# custom_hat_v_alpha.net
KiCad netlist of a schematic drawn in EAGLE
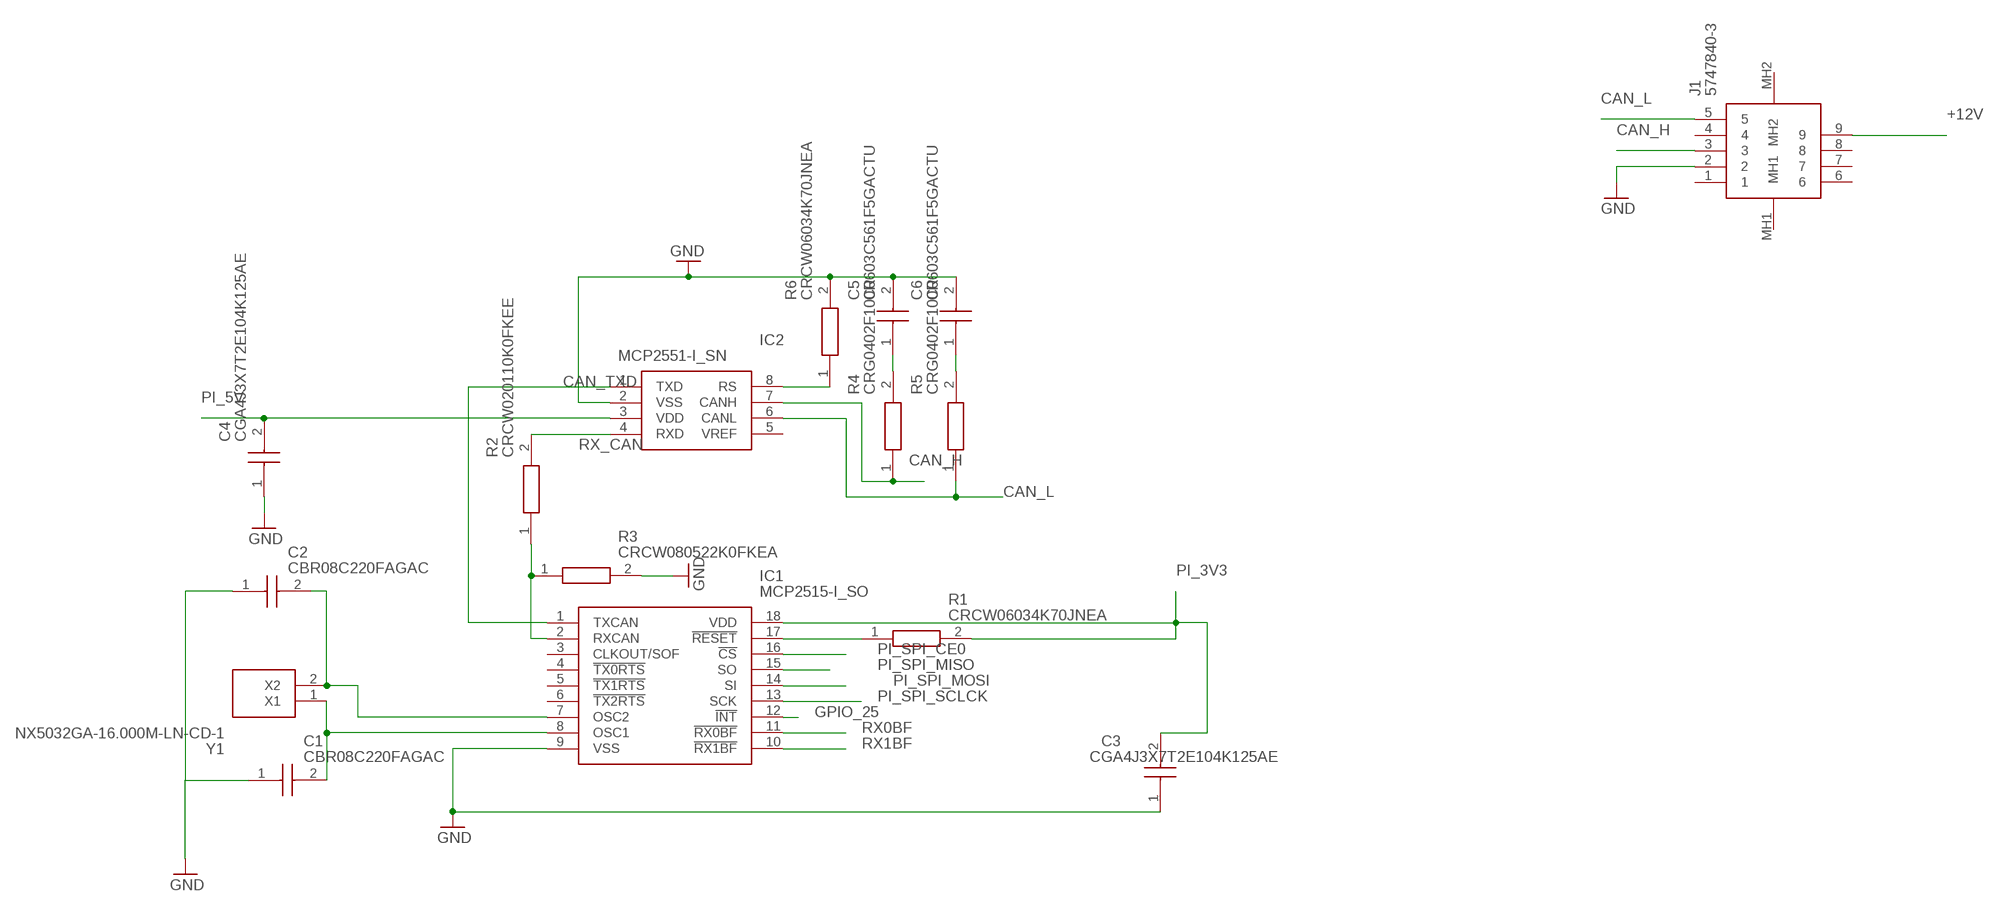
[diagram p0: schematic, sheet 1]

(export (version "E")
  (design (tool "Eeschema 10.0.6"))
  (components
    (comp (ref "C1")
      (value "CBR08C220FAGAC")
      (footprint "eagle-import:CAPC2012X95N")
      (libsource (lib "eagle-import") (part "CBR08C220FAGAC"))
    )
    (comp (ref "C2")
      (value "CBR08C220FAGAC")
      (footprint "eagle-import:CAPC2012X95N")
      (libsource (lib "eagle-import") (part "CBR08C220FAGAC"))
    )
    (comp (ref "C3")
      (value "CGA4J3X7T2E104K125AE")
      (footprint "eagle-import:CAPC2012X145N")
      (fields (field (name "MOUSER_PART_NUMBER") "810-CGA4J3X7T2E104KS"))
      (libsource (lib "eagle-import") (part "CGA4J3X7T2E104K125AE"))
    )
    (comp (ref "C4")
      (value "CGA4J3X7T2E104K125AE")
      (footprint "eagle-import:CAPC2012X145N")
      (fields (field (name "MOUSER_PART_NUMBER") "810-CGA4J3X7T2E104KS"))
      (libsource (lib "eagle-import") (part "CGA4J3X7T2E104K125AE"))
    )
    (comp (ref "C5")
      (value "C0603C561F5GACTU")
      (footprint "eagle-import:CAPC1608X87N")
      (fields (field (name "MOUSER_PART_NUMBER") "80-C0603C561F5G"))
      (libsource (lib "eagle-import") (part "C0603C561F5GACTU"))
    )
    (comp (ref "C6")
      (value "C0603C561F5GACTU")
      (footprint "eagle-import:CAPC1608X87N")
      (fields (field (name "MOUSER_PART_NUMBER") "80-C0603C561F5G"))
      (libsource (lib "eagle-import") (part "C0603C561F5GACTU"))
    )
    (comp (ref "IC1")
      (value "MCP2515-I_SO")
      (footprint "eagle-import:SOIC127P1030X265-18N")
      (fields
        (field (name "ARROW_PART_NUMBER") "MCP2515-I/SO")
        (field (name "MOUSER_PART_NUMBER") "579-MCP2515-I/SO")
      )
      (libsource (lib "eagle-import") (part "MCP2515-I_SO"))
    )
    (comp (ref "IC2")
      (value "MCP2551-I_SN")
      (footprint "eagle-import:SOIC127P600X175-8N")
      (fields
        (field (name "ARROW_PART_NUMBER") "MCP2551-I/SN")
        (field (name "MOUSER_PART_NUMBER") "579-MCP2551-I/SN")
      )
      (libsource (lib "eagle-import") (part "MCP2551-I_SN"))
    )
    (comp (ref "J1")
      (value "5747840-3")
      (footprint "eagle-import:57478403")
      (fields (field (name "MOUSER_PART_NUMBER") "571-5747840-3"))
      (libsource (lib "eagle-import") (part "5747840-3"))
    )
    (comp (ref "R1")
      (value "CRCW06034K70JNEA")
      (footprint "eagle-import:RESC1608X50N")
      (fields (field (name "MOUSER_PART_NUMBER") "71-CRCW0603J-4.7K-E3"))
      (libsource (lib "eagle-import") (part "CRCW06034K70JNEA"))
    )
    (comp (ref "R2")
      (value "CRCW020110K0FKEE")
      (footprint "eagle-import:RESC0603X28N")
      (libsource (lib "eagle-import") (part "CRCW020110K0FKEE"))
    )
    (comp (ref "R3")
      (value "CRCW080522K0FKEA")
      (footprint "eagle-import:RESC2012X50N")
      (fields (field (name "MOUSER_PART_NUMBER") "71-CRCW0805-22K-E3"))
      (libsource (lib "eagle-import") (part "CRCW080522K0FKEA"))
    )
    (comp (ref "R4")
      (value "CRG0402F100R")
      (footprint "eagle-import:RESC1005X40N")
      (fields (field (name "MOUSER_PART_NUMBER") "279-CRG0402F100R"))
      (libsource (lib "eagle-import") (part "CRG0402F100R"))
    )
    (comp (ref "R5")
      (value "CRG0402F100R")
      (footprint "eagle-import:RESC1005X40N")
      (fields (field (name "MOUSER_PART_NUMBER") "279-CRG0402F100R"))
      (libsource (lib "eagle-import") (part "CRG0402F100R"))
    )
    (comp (ref "R6")
      (value "CRCW06034K70JNEA")
      (footprint "eagle-import:RESC1608X50N")
      (fields (field (name "MOUSER_PART_NUMBER") "71-CRCW0603J-4.7K-E3"))
      (libsource (lib "eagle-import") (part "CRCW06034K70JNEA"))
    )
    (comp (ref "Y1")
      (value "NX5032GA-16.000M-LN-CD-1")
      (footprint "eagle-import:NX5032GA16000000MHZLNCD1")
      (fields (field (name "MOUSER_PART_NUMBER") "344-NX5032GA16MLNCD1"))
      (libsource (lib "eagle-import") (part "NX5032GA-16.000M-LN-CD-1"))
    )
  )
  (nets
    (net (code "1") (name "/+12V") (class "Default")
      (node (ref "J1") (pin "9") (pinfunction "9_9") (pintype "bidirectional"))
    )
    (net (code "2") (name "/CAN_H") (class "Default")
      (node (ref "IC2") (pin "7") (pinfunction "CANH_7") (pintype "bidirectional"))
      (node (ref "J1") (pin "3") (pinfunction "3_3") (pintype "bidirectional"))
      (node (ref "R4") (pin "1") (pinfunction "1_1") (pintype "bidirectional"))
    )
    (net (code "3") (name "/CAN_L") (class "Default")
      (node (ref "IC2") (pin "6") (pinfunction "CANL_6") (pintype "bidirectional"))
      (node (ref "J1") (pin "5") (pinfunction "5_5") (pintype "bidirectional"))
      (node (ref "R5") (pin "1") (pinfunction "1_1") (pintype "bidirectional"))
    )
    (net (code "4") (name "/CAN_TXD") (class "Default")
      (node (ref "IC1") (pin "1") (pinfunction "TXCAN_1") (pintype "bidirectional"))
      (node (ref "IC2") (pin "1") (pinfunction "TXD_1") (pintype "bidirectional"))
    )
    (net (code "5") (name "/GPIO_25") (class "Default")
      (node (ref "IC1") (pin "12") (pinfunction "~{INT}_12") (pintype "bidirectional"))
    )
    (net (code "6") (name "/PI_3V3") (class "Default")
      (node (ref "C3") (pin "2") (pinfunction "2_2") (pintype "bidirectional"))
      (node (ref "IC1") (pin "18") (pinfunction "VDD_18") (pintype "bidirectional"))
      (node (ref "R1") (pin "2") (pinfunction "2_2") (pintype "bidirectional"))
    )
    (net (code "7") (name "/PI_5V") (class "Default")
      (node (ref "C4") (pin "2") (pinfunction "2_2") (pintype "bidirectional"))
      (node (ref "IC2") (pin "3") (pinfunction "VDD_3") (pintype "bidirectional"))
    )
    (net (code "8") (name "/PI_SPI_CE0") (class "Default")
      (node (ref "IC1") (pin "16") (pinfunction "~{CS}_16") (pintype "bidirectional"))
    )
    (net (code "9") (name "/PI_SPI_MISO") (class "Default")
      (node (ref "IC1") (pin "15") (pinfunction "SO_15") (pintype "bidirectional"))
    )
    (net (code "10") (name "/PI_SPI_MOSI") (class "Default")
      (node (ref "IC1") (pin "14") (pinfunction "SI_14") (pintype "bidirectional"))
    )
    (net (code "11") (name "/PI_SPI_SCLCK") (class "Default")
      (node (ref "IC1") (pin "13") (pinfunction "SCK_13") (pintype "bidirectional"))
    )
    (net (code "12") (name "/RX0BF") (class "Default")
      (node (ref "IC1") (pin "11") (pinfunction "~{RX0BF}_11") (pintype "bidirectional"))
    )
    (net (code "13") (name "/RX1BF") (class "Default")
      (node (ref "IC1") (pin "10") (pinfunction "~{RX1BF}_10") (pintype "bidirectional"))
    )
    (net (code "14") (name "/RX_CAN") (class "Default")
      (node (ref "IC2") (pin "4") (pinfunction "RXD_4") (pintype "bidirectional"))
      (node (ref "R2") (pin "2") (pinfunction "2_2") (pintype "bidirectional"))
    )
    (net (code "15") (name "GND") (class "Default")
      (node (ref "C1") (pin "1") (pinfunction "1_1") (pintype "bidirectional"))
      (node (ref "C2") (pin "1") (pinfunction "1_1") (pintype "bidirectional"))
      (node (ref "C3") (pin "1") (pinfunction "1_1") (pintype "bidirectional"))
      (node (ref "C4") (pin "1") (pinfunction "1_1") (pintype "bidirectional"))
      (node (ref "C5") (pin "2") (pinfunction "2_2") (pintype "bidirectional"))
      (node (ref "C6") (pin "2") (pinfunction "2_2") (pintype "bidirectional"))
      (node (ref "IC1") (pin "9") (pinfunction "VSS_9") (pintype "bidirectional"))
      (node (ref "IC2") (pin "2") (pinfunction "VSS_2") (pintype "bidirectional"))
      (node (ref "J1") (pin "2") (pinfunction "2_2") (pintype "bidirectional"))
      (node (ref "R3") (pin "2") (pinfunction "2_2") (pintype "bidirectional"))
      (node (ref "R6") (pin "2") (pinfunction "2_2") (pintype "bidirectional"))
    )
    (net (code "16") (name "Net-(C5-Pad1)") (class "Default")
      (node (ref "C5") (pin "1") (pinfunction "1_1") (pintype "bidirectional"))
      (node (ref "R4") (pin "2") (pinfunction "2_2") (pintype "bidirectional"))
    )
    (net (code "17") (name "Net-(C6-Pad1)") (class "Default")
      (node (ref "C6") (pin "1") (pinfunction "1_1") (pintype "bidirectional"))
      (node (ref "R5") (pin "2") (pinfunction "2_2") (pintype "bidirectional"))
    )
    (net (code "18") (name "Net-(IC1-OSC1)") (class "Default")
      (node (ref "C1") (pin "2") (pinfunction "2_2") (pintype "bidirectional"))
      (node (ref "IC1") (pin "8") (pinfunction "OSC1_8") (pintype "bidirectional"))
      (node (ref "Y1") (pin "1") (pinfunction "X1_1") (pintype "bidirectional"))
    )
    (net (code "19") (name "Net-(IC1-OSC2)") (class "Default")
      (node (ref "C2") (pin "2") (pinfunction "2_2") (pintype "bidirectional"))
      (node (ref "IC1") (pin "7") (pinfunction "OSC2_7") (pintype "bidirectional"))
      (node (ref "Y1") (pin "2") (pinfunction "X2_2") (pintype "bidirectional"))
    )
    (net (code "20") (name "Net-(IC1-RXCAN)") (class "Default")
      (node (ref "IC1") (pin "2") (pinfunction "RXCAN_2") (pintype "bidirectional"))
      (node (ref "R2") (pin "1") (pinfunction "1_1") (pintype "bidirectional"))
      (node (ref "R3") (pin "1") (pinfunction "1_1") (pintype "bidirectional"))
    )
    (net (code "21") (name "Net-(IC1-~{RESET})") (class "Default")
      (node (ref "IC1") (pin "17") (pinfunction "~{RESET}_17") (pintype "bidirectional"))
      (node (ref "R1") (pin "1") (pinfunction "1_1") (pintype "bidirectional"))
    )
    (net (code "22") (name "Net-(IC2-RS)") (class "Default")
      (node (ref "IC2") (pin "8") (pinfunction "RS_8") (pintype "bidirectional"))
      (node (ref "R6") (pin "1") (pinfunction "1_1") (pintype "bidirectional"))
    )
    (net (code "23") (name "unconnected-(IC1-CLKOUT{slash}SOF-Pad3)") (class "Default")
      (node (ref "IC1") (pin "3") (pinfunction "CLKOUT/SOF_3") (pintype "bidirectional"))
    )
    (net (code "24") (name "unconnected-(IC1-~{TX0RTS}-Pad4)") (class "Default")
      (node (ref "IC1") (pin "4") (pinfunction "~{TX0RTS}_4") (pintype "bidirectional"))
    )
    (net (code "25") (name "unconnected-(IC1-~{TX1RTS}-Pad5)") (class "Default")
      (node (ref "IC1") (pin "5") (pinfunction "~{TX1RTS}_5") (pintype "bidirectional"))
    )
    (net (code "26") (name "unconnected-(IC1-~{TX2RTS}-Pad6)") (class "Default")
      (node (ref "IC1") (pin "6") (pinfunction "~{TX2RTS}_6") (pintype "bidirectional"))
    )
    (net (code "27") (name "unconnected-(IC2-VREF-Pad5)") (class "Default")
      (node (ref "IC2") (pin "5") (pinfunction "VREF_5") (pintype "bidirectional"))
    )
    (net (code "28") (name "unconnected-(J1-Pad1)") (class "Default")
      (node (ref "J1") (pin "1") (pinfunction "1_1") (pintype "bidirectional"))
    )
    (net (code "29") (name "unconnected-(J1-Pad4)") (class "Default")
      (node (ref "J1") (pin "4") (pinfunction "4_4") (pintype "bidirectional"))
    )
    (net (code "30") (name "unconnected-(J1-Pad6)") (class "Default")
      (node (ref "J1") (pin "6") (pinfunction "6_6") (pintype "bidirectional"))
    )
    (net (code "31") (name "unconnected-(J1-Pad7)") (class "Default")
      (node (ref "J1") (pin "7") (pinfunction "7_7") (pintype "bidirectional"))
    )
    (net (code "32") (name "unconnected-(J1-Pad8)") (class "Default")
      (node (ref "J1") (pin "8") (pinfunction "8_8") (pintype "bidirectional"))
    )
    (net (code "33") (name "unconnected-(J1-PadMH1)") (class "Default")
      (node (ref "J1") (pin "MH1") (pinfunction "MH1_MH1") (pintype "bidirectional"))
    )
    (net (code "34") (name "unconnected-(J1-PadMH2)") (class "Default")
      (node (ref "J1") (pin "MH2") (pinfunction "MH2_MH2") (pintype "bidirectional"))
    )
  )
)
